# OSO-RING-A2-00.net
KiCad netlist of a schematic drawn in EAGLE
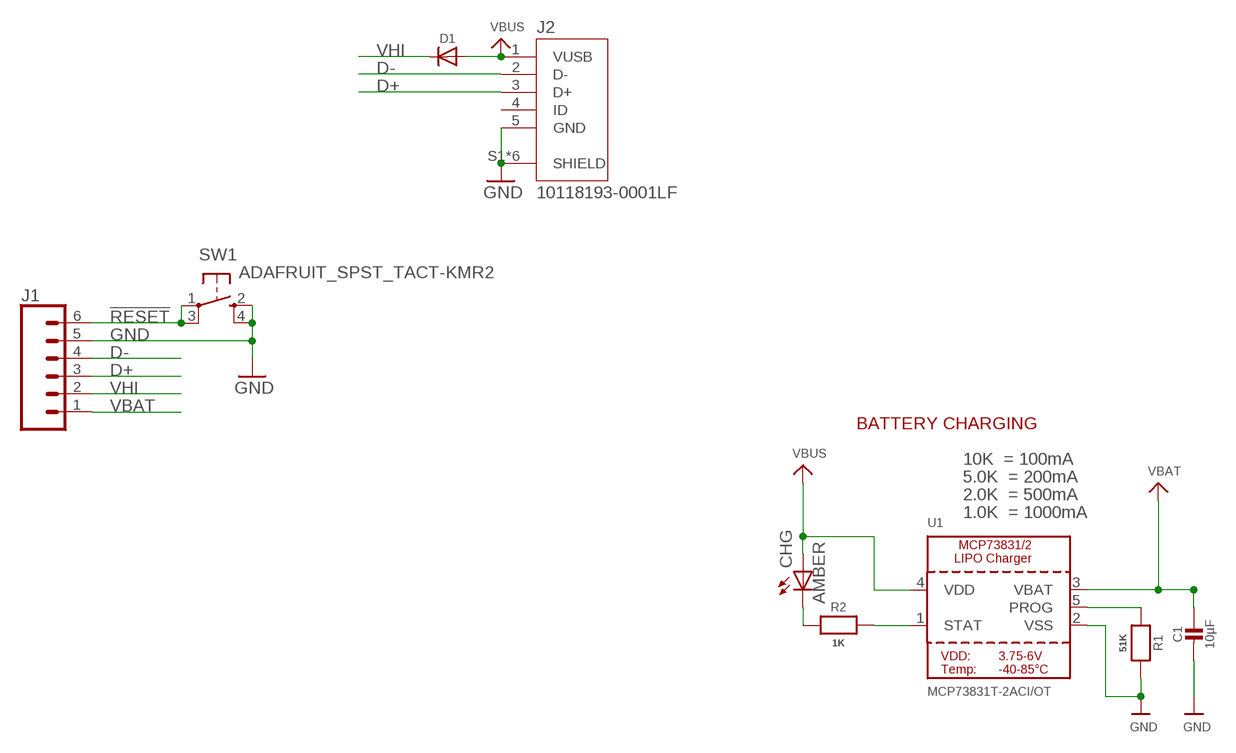
[diagram p0: schematic, sheet 1]

(export (version "E")
  (design (tool "Eeschema 10.0.6"))
  (components
    (comp (ref "C1")
      (value "10µF")
      (footprint "eagle-import:0805-NO")
      (libsource (lib "eagle-import") (part "CAP_CERAMIC0805-NOOUTLINE"))
    )
    (comp (ref "CHG")
      (value "AMBER")
      (footprint "eagle-import:CHIPLED_0805")
      (libsource (lib "eagle-import") (part "LEDCHIPLED_0805"))
    )
    (comp (ref "D1")
      (value "MICROBUILDER_DIODESOD-123")
      (footprint "eagle-import:MICROBUILDER_SOD-123")
      (libsource (lib "eagle-import") (part "MICROBUILDER_DIODESOD-123"))
    )
    (comp (ref "J1")
      (value "CONN_06SMD-1MM")
      (footprint "eagle-import:1X06-1MM")
      (libsource (lib "eagle-import") (part "CONN_06SMD-1MM"))
    )
    (comp (ref "J2")
      (value "10118193-0001LF")
      (footprint "eagle-import:FCI_10118193-0001LF")
      (fields (field (name "DIGI-KEY_PART_NUMBER") "609-4616-1-ND") (field (name "MF") "Amphenol ICC"))
      (libsource (lib "eagle-import") (part "10118193-0001LF"))
    )
    (comp (ref "R1")
      (value "51K")
      (footprint "eagle-import:0805-NO")
      (libsource (lib "eagle-import") (part "RESISTOR0805_NOOUTLINE"))
    )
    (comp (ref "R2")
      (value "1K")
      (footprint "eagle-import:0805-NO")
      (libsource (lib "eagle-import") (part "RESISTOR0805_NOOUTLINE"))
    )
    (comp (ref "SW1")
      (value "ADAFRUIT_SPST_TACT-KMR2")
      (footprint "eagle-import:ADAFRUIT_KMR2")
      (libsource (lib "eagle-import") (part "ADAFRUIT_SPST_TACT-KMR2"))
    )
    (comp (ref "U1")
      (value "MCP73831T-2ACI/OT")
      (footprint "eagle-import:SOT23-5")
      (libsource (lib "eagle-import") (part "MCP73831/2"))
    )
  )
  (nets
    (net (code "1") (name "/D+") (class "Default")
      (node (ref "J1") (pin "3") (pinfunction "3_3") (pintype "passive"))
      (node (ref "J2") (pin "3") (pinfunction "D+_3") (pintype "passive"))
    )
    (net (code "2") (name "/D-") (class "Default")
      (node (ref "J1") (pin "4") (pinfunction "4_4") (pintype "passive"))
      (node (ref "J2") (pin "2") (pinfunction "D-_2") (pintype "passive"))
    )
    (net (code "3") (name "/VHI") (class "Default")
      (node (ref "D1") (pin "C") (pinfunction "C_C") (pintype "passive"))
      (node (ref "J1") (pin "2") (pinfunction "2_2") (pintype "passive"))
    )
    (net (code "4") (name "/~{RESET}") (class "Default")
      (node (ref "J1") (pin "6") (pinfunction "6_6") (pintype "passive"))
      (node (ref "SW1") (pin "1") (pinfunction "P_1") (pintype "passive"))
      (node (ref "SW1") (pin "3") (pinfunction "P1_3") (pintype "passive"))
    )
    (net (code "5") (name "GND") (class "Default")
      (node (ref "C1") (pin "2") (pinfunction "2_2") (pintype "passive"))
      (node (ref "J1") (pin "5") (pinfunction "5_5") (pintype "passive"))
      (node (ref "J2") (pin "5") (pinfunction "GND_5") (pintype "passive"))
      (node (ref "J2") (pin "S1") (pinfunction "SHIELD_S1") (pintype "passive"))
      (node (ref "J2") (pin "S2") (pinfunction "SHIELD_S2") (pintype "passive"))
      (node (ref "J2") (pin "S3") (pinfunction "SHIELD_S3") (pintype "passive"))
      (node (ref "J2") (pin "S4") (pinfunction "SHIELD_S4") (pintype "passive"))
      (node (ref "J2") (pin "S5") (pinfunction "SHIELD_S5") (pintype "passive"))
      (node (ref "J2") (pin "S6") (pinfunction "SHIELD_S6") (pintype "passive"))
      (node (ref "R1") (pin "2") (pinfunction "2_2") (pintype "passive"))
      (node (ref "SW1") (pin "2") (pinfunction "S_2") (pintype "passive"))
      (node (ref "SW1") (pin "4") (pinfunction "S1_4") (pintype "passive"))
      (node (ref "U1") (pin "2") (pinfunction "VSS_2") (pintype "power_in"))
    )
    (net (code "6") (name "Net-(CHG-PadC)") (class "Default")
      (node (ref "CHG") (pin "C") (pinfunction "C_C") (pintype "passive"))
      (node (ref "R2") (pin "1") (pinfunction "1_1") (pintype "passive"))
    )
    (net (code "7") (name "Net-(U1-PROG)") (class "Default")
      (node (ref "R1") (pin "1") (pinfunction "1_1") (pintype "passive"))
      (node (ref "U1") (pin "5") (pinfunction "PROG_5") (pintype "input"))
    )
    (net (code "8") (name "Net-(U1-STAT)") (class "Default")
      (node (ref "R2") (pin "2") (pinfunction "2_2") (pintype "passive"))
      (node (ref "U1") (pin "1") (pinfunction "STAT_1") (pintype "output"))
    )
    (net (code "9") (name "VBAT") (class "Default")
      (node (ref "C1") (pin "1") (pinfunction "1_1") (pintype "passive"))
      (node (ref "J1") (pin "1") (pinfunction "1_1") (pintype "passive"))
      (node (ref "U1") (pin "3") (pinfunction "VBAT_3") (pintype "power_in"))
    )
    (net (code "10") (name "VBUS") (class "Default")
      (node (ref "CHG") (pin "A") (pinfunction "A_A") (pintype "passive"))
      (node (ref "D1") (pin "A") (pinfunction "A_A") (pintype "passive"))
      (node (ref "J2") (pin "1") (pinfunction "VUSB_1") (pintype "passive"))
      (node (ref "U1") (pin "4") (pinfunction "VDD_4") (pintype "power_in"))
    )
    (net (code "11") (name "unconnected-(J2-ID-Pad4)") (class "Default")
      (node (ref "J2") (pin "4") (pinfunction "ID_4") (pintype "passive"))
    )
  )
)
